# baskettarget.net
KiCad netlist of a schematic drawn in EAGLE
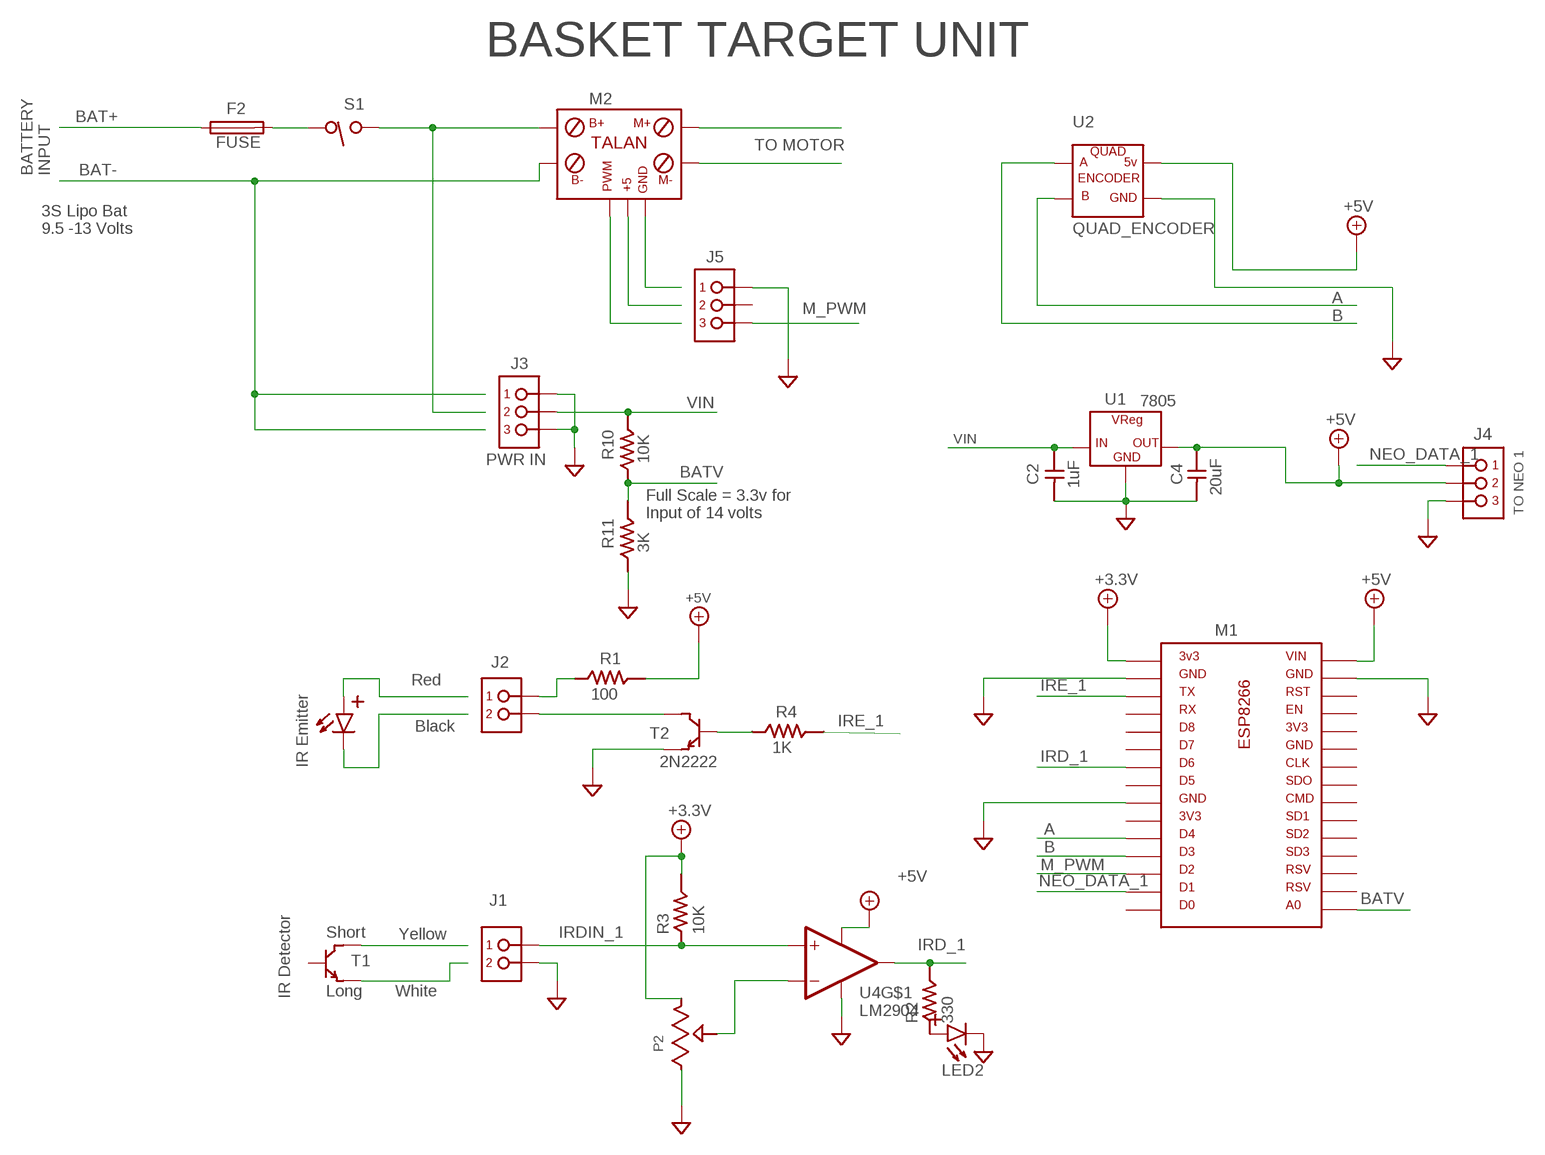
[diagram p0: schematic, sheet 1]

(export (version "E")
  (design (tool "Eeschema 10.0.6"))
  (components
    (comp (ref "C2")
      (value "1uF")
      (footprint "eagle-import:CAP200")
      (libsource (lib "eagle-import") (part "CAP200"))
    )
    (comp (ref "C4")
      (value "20uF")
      (footprint "eagle-import:CAP200")
      (libsource (lib "eagle-import") (part "CAP200"))
    )
    (comp (ref "F2")
      (value "FUSE")
      (footprint "eagle-import:FUSE_HOLDER_WICKMANN-19596")
      (libsource (lib "eagle-import") (part "FUSE19596"))
    )
    (comp (ref "J1")
      (value "PINHDR_1X2-JST")
      (footprint "eagle-import:JST-XH_098_VERT_1X2")
      (libsource (lib "eagle-import") (part "PINHDR_1X2-JST"))
    )
    (comp (ref "J2")
      (value "PINHDR_1X2-JST")
      (footprint "eagle-import:JST-XH_098_VERT_1X2")
      (libsource (lib "eagle-import") (part "PINHDR_1X2-JST"))
    )
    (comp (ref "J3")
      (value "PINHDR_1X3XH-JST")
      (footprint "eagle-import:JST-XH_098_VERT_1X3")
      (libsource (lib "eagle-import") (part "PINHDR_1X3-JSTXH"))
    )
    (comp (ref "J4")
      (value "PINHDR_1X3XH-JST")
      (footprint "eagle-import:JST-XH_098_VERT_1X3")
      (libsource (lib "eagle-import") (part "PINHDR_1X3-JSTXH"))
    )
    (comp (ref "J5")
      (value "PINHDR_1X3XH-JST")
      (footprint "eagle-import:JST-XH_098_VERT_1X3")
      (libsource (lib "eagle-import") (part "PINHDR_1X3-JSTXH"))
    )
    (comp (ref "LED1")
      (value "LEDTH-DIP-100")
      (footprint "eagle-import:LED-TH100")
      (libsource (lib "eagle-import") (part "LEDTH-DIP-100"))
    )
    (comp (ref "LED2")
      (value "LEDTH-DIP-100")
      (footprint "eagle-import:LED-TH100")
      (libsource (lib "eagle-import") (part "LEDTH-DIP-100"))
    )
    (comp (ref "M1")
      (value "ESP8266_MODULE")
      (footprint "eagle-import:ESP8266_MODULE")
      (libsource (lib "eagle-import") (part "ESP8266_MODULE"))
    )
    (comp (ref "M2")
      (value "TALAN")
      (footprint "eagle-import:TALAN_PWM")
      (libsource (lib "eagle-import") (part "TALAN"))
    )
    (comp (ref "P2")
      (value "TRIMPOT-SIP")
      (footprint "eagle-import:TRIMPOT_SIP_100")
      (libsource (lib "eagle-import") (part "TRIMPOT-SIP"))
    )
    (comp (ref "R1")
      (value "100")
      (footprint "eagle-import:R300")
      (libsource (lib "eagle-import") (part "RTHOLE300"))
    )
    (comp (ref "R2")
      (value "330")
      (footprint "eagle-import:R300")
      (libsource (lib "eagle-import") (part "RTHOLE300"))
    )
    (comp (ref "R3")
      (value "10K")
      (footprint "eagle-import:R300")
      (libsource (lib "eagle-import") (part "RTHOLE300"))
    )
    (comp (ref "R4")
      (value "1K")
      (footprint "eagle-import:R300")
      (libsource (lib "eagle-import") (part "RTHOLE300"))
    )
    (comp (ref "R10")
      (value "10K")
      (footprint "eagle-import:R300")
      (libsource (lib "eagle-import") (part "RTHOLE300"))
    )
    (comp (ref "R11")
      (value "3K")
      (footprint "eagle-import:R300")
      (libsource (lib "eagle-import") (part "RTHOLE300"))
    )
    (comp (ref "S1")
      (value "TOGGLE_SWITCH_SPST")
      (footprint "eagle-import:SPST_TOGGLE")
      (libsource (lib "eagle-import") (part "TOGGLE_SWITCH_SPST"))
    )
    (comp (ref "T1")
      (value "T_NPN")
      (footprint "eagle-import:TO-92")
      (libsource (lib "eagle-import") (part "T_NPN"))
    )
    (comp (ref "T2")
      (value "2N2222")
      (footprint "eagle-import:TO-92")
      (libsource (lib "eagle-import") (part "T_NPN"))
    )
    (comp (ref "U1")
      (value "7805")
      (footprint "eagle-import:PINHDR_TH_100_1X3")
      (libsource (lib "eagle-import") (part "VREG-3-DIP"))
    )
    (comp (ref "U2")
      (value "QUAD_ENCODER")
      (footprint "eagle-import:QUAD_ENCODER")
      (libsource (lib "eagle-import") (part "QUAD_ENCODER"))
    )
    (comp (ref "U4")
      (value "LM2904")
      (footprint "eagle-import:DIP8")
      (libsource (lib "eagle-import") (part "LM2904"))
    )
  )
  (nets
    (net (code "1") (name "+3.3V") (class "Default")
      (node (ref "M1") (pin "P$1") (pinfunction "P$1_P$1") (pintype "passive"))
      (node (ref "P2") (pin "P$3") (pinfunction "P$3_P$3") (pintype "passive"))
      (node (ref "R3") (pin "P$2") (pinfunction "2_P$2") (pintype "passive"))
    )
    (net (code "2") (name "+5V") (class "Default")
      (node (ref "C4") (pin "2") (pinfunction "2_2") (pintype "passive"))
      (node (ref "J4") (pin "2") (pinfunction "2_2") (pintype "passive"))
      (node (ref "M1") (pin "P$30") (pinfunction "P$30_P$30") (pintype "passive"))
      (node (ref "R1") (pin "P$2") (pinfunction "2_P$2") (pintype "passive"))
      (node (ref "U1") (pin "3") (pinfunction "OUT_3") (pintype "passive"))
      (node (ref "U2") (pin "5V") (pinfunction "5V_5V") (pintype "passive"))
      (node (ref "U4") (pin "P$8") (pinfunction "P+_P$8") (pintype "passive"))
    )
    (net (code "3") (name "/A") (class "Default")
      (node (ref "M1") (pin "P$11") (pinfunction "P$11_P$11") (pintype "passive"))
      (node (ref "U2") (pin "B") (pinfunction "B_B") (pintype "passive"))
    )
    (net (code "4") (name "/B") (class "Default")
      (node (ref "M1") (pin "P$12") (pinfunction "P$12_P$12") (pintype "passive"))
      (node (ref "U2") (pin "A") (pinfunction "A_A") (pintype "passive"))
    )
    (net (code "5") (name "/BAT+") (class "Default")
      (node (ref "F2") (pin "A") (pinfunction "1_A") (pintype "passive"))
    )
    (net (code "6") (name "/BAT-") (class "Default")
      (node (ref "M2") (pin "B-") (pinfunction "B-_B-") (pintype "passive"))
    )
    (net (code "7") (name "/BATV") (class "Default")
      (node (ref "M1") (pin "P$16") (pinfunction "P$16_P$16") (pintype "passive"))
      (node (ref "R10") (pin "P$1") (pinfunction "1_P$1") (pintype "passive"))
      (node (ref "R11") (pin "P$2") (pinfunction "2_P$2") (pintype "passive"))
    )
    (net (code "8") (name "/IRDIN_1") (class "Default")
      (node (ref "J1") (pin "1") (pinfunction "1_1") (pintype "passive"))
      (node (ref "R3") (pin "P$1") (pinfunction "1_P$1") (pintype "passive"))
      (node (ref "U4") (pin "P$3") (pinfunction "+IN_P$3") (pintype "input"))
    )
    (net (code "9") (name "/IRD_1") (class "Default")
      (node (ref "M1") (pin "P$7") (pinfunction "P$7_P$7") (pintype "passive"))
      (node (ref "R2") (pin "P$2") (pinfunction "2_P$2") (pintype "passive"))
      (node (ref "U4") (pin "P$1") (pinfunction "OUT_P$1") (pintype "output"))
    )
    (net (code "10") (name "/IRE_1") (class "Default")
      (node (ref "M1") (pin "P$3") (pinfunction "P$3_P$3") (pintype "passive"))
      (node (ref "R4") (pin "P$2") (pinfunction "2_P$2") (pintype "passive"))
    )
    (net (code "11") (name "/M_PWM") (class "Default")
      (node (ref "J5") (pin "1") (pinfunction "3_1") (pintype "passive"))
      (node (ref "M1") (pin "P$13") (pinfunction "P$13_P$13") (pintype "passive"))
    )
    (net (code "12") (name "/NEO_DATA_1") (class "Default")
      (node (ref "J4") (pin "3") (pinfunction "1_3") (pintype "passive"))
      (node (ref "M1") (pin "P$14") (pinfunction "P$14_P$14") (pintype "passive"))
    )
    (net (code "13") (name "/VIN") (class "Default")
      (node (ref "C2") (pin "2") (pinfunction "2_2") (pintype "passive"))
      (node (ref "J3") (pin "2") (pinfunction "2_2") (pintype "passive"))
      (node (ref "R10") (pin "P$2") (pinfunction "2_P$2") (pintype "passive"))
      (node (ref "U1") (pin "1") (pinfunction "IN_1") (pintype "passive"))
    )
    (net (code "14") (name "GND") (class "Default")
      (node (ref "C2") (pin "1") (pinfunction "1_1") (pintype "passive"))
      (node (ref "C4") (pin "1") (pinfunction "1_1") (pintype "passive"))
      (node (ref "J1") (pin "2") (pinfunction "2_2") (pintype "passive"))
      (node (ref "J3") (pin "1") (pinfunction "3_1") (pintype "passive"))
      (node (ref "J3") (pin "3") (pinfunction "1_3") (pintype "passive"))
      (node (ref "J4") (pin "1") (pinfunction "3_1") (pintype "passive"))
      (node (ref "J5") (pin "3") (pinfunction "1_3") (pintype "passive"))
      (node (ref "LED2") (pin "P$2") (pinfunction "CATHODE_P$2") (pintype "passive"))
      (node (ref "M1") (pin "P$2") (pinfunction "P$2_P$2") (pintype "passive"))
      (node (ref "M1") (pin "P$29") (pinfunction "P$29_P$29") (pintype "passive"))
      (node (ref "M1") (pin "P$9") (pinfunction "P$9_P$9") (pintype "passive"))
      (node (ref "P2") (pin "P$1") (pinfunction "P$1_P$1") (pintype "passive"))
      (node (ref "R11") (pin "P$1") (pinfunction "1_P$1") (pintype "passive"))
      (node (ref "T2") (pin "P$3") (pinfunction "EMITTER_P$3") (pintype "passive"))
      (node (ref "U1") (pin "2") (pinfunction "GND_2") (pintype "passive"))
      (node (ref "U2") (pin "GND") (pinfunction "GND_GND") (pintype "passive"))
      (node (ref "U4") (pin "P$4") (pinfunction "P-_P$4") (pintype "passive"))
    )
    (net (code "15") (name "Net-(F2-2)") (class "Default")
      (node (ref "F2") (pin "B") (pinfunction "2_B") (pintype "passive"))
      (node (ref "S1") (pin "P$1") (pinfunction "P$1_P$1") (pintype "passive"))
    )
    (net (code "16") (name "Net-(LED2-ANODE)") (class "Default")
      (node (ref "LED2") (pin "P$1") (pinfunction "ANODE_P$1") (pintype "passive"))
      (node (ref "R2") (pin "P$1") (pinfunction "1_P$1") (pintype "passive"))
    )
    (net (code "17") (name "Net-(M2-PadB+)") (class "Default")
      (node (ref "M2") (pin "B+") (pinfunction "B+_B+") (pintype "passive"))
      (node (ref "S1") (pin "P$3") (pinfunction "P$3_P$3") (pintype "passive"))
    )
    (net (code "18") (name "Net-(R1-1)") (class "Default")
      (node (ref "J2") (pin "1") (pinfunction "1_1") (pintype "passive"))
      (node (ref "R1") (pin "P$1") (pinfunction "1_P$1") (pintype "passive"))
    )
    (net (code "19") (name "Net-(R4-1)") (class "Default")
      (node (ref "R4") (pin "P$1") (pinfunction "1_P$1") (pintype "passive"))
      (node (ref "T2") (pin "P$2") (pinfunction "BASE_P$2") (pintype "passive"))
    )
    (net (code "20") (name "Net-(T2-COLLECTOR)") (class "Default")
      (node (ref "J2") (pin "2") (pinfunction "2_2") (pintype "passive"))
      (node (ref "T2") (pin "P$1") (pinfunction "COLLECTOR_P$1") (pintype "passive"))
    )
    (net (code "21") (name "Net-(U4A--IN)") (class "Default")
      (node (ref "P2") (pin "P$2") (pinfunction "P$2_P$2") (pintype "passive"))
      (node (ref "U4") (pin "P$2") (pinfunction "-IN_P$2") (pintype "input"))
    )
    (net (code "22") (name "unconnected-(J5-Pad2)") (class "Default")
      (node (ref "J5") (pin "2") (pinfunction "2_2") (pintype "passive"))
    )
    (net (code "23") (name "unconnected-(LED1-ANODE-PadP$1)") (class "Default")
      (node (ref "LED1") (pin "P$1") (pinfunction "ANODE_P$1") (pintype "passive"))
    )
    (net (code "24") (name "unconnected-(LED1-CATHODE-PadP$2)") (class "Default")
      (node (ref "LED1") (pin "P$2") (pinfunction "CATHODE_P$2") (pintype "passive"))
    )
    (net (code "25") (name "unconnected-(M1-PadP$4)") (class "Default")
      (node (ref "M1") (pin "P$4") (pinfunction "P$4_P$4") (pintype "passive"))
    )
    (net (code "26") (name "unconnected-(M1-PadP$5)") (class "Default")
      (node (ref "M1") (pin "P$5") (pinfunction "P$5_P$5") (pintype "passive"))
    )
    (net (code "27") (name "unconnected-(M1-PadP$6)") (class "Default")
      (node (ref "M1") (pin "P$6") (pinfunction "P$6_P$6") (pintype "passive"))
    )
    (net (code "28") (name "unconnected-(M1-PadP$8)") (class "Default")
      (node (ref "M1") (pin "P$8") (pinfunction "P$8_P$8") (pintype "passive"))
    )
    (net (code "29") (name "unconnected-(M1-PadP$10)") (class "Default")
      (node (ref "M1") (pin "P$10") (pinfunction "P$10_P$10") (pintype "passive"))
    )
    (net (code "30") (name "unconnected-(M1-PadP$15)") (class "Default")
      (node (ref "M1") (pin "P$15") (pinfunction "P$15_P$15") (pintype "passive"))
    )
    (net (code "31") (name "unconnected-(M1-PadP$17)") (class "Default")
      (node (ref "M1") (pin "P$17") (pinfunction "P$17_P$17") (pintype "passive"))
    )
    (net (code "32") (name "unconnected-(M1-PadP$18)") (class "Default")
      (node (ref "M1") (pin "P$18") (pinfunction "P$18_P$18") (pintype "passive"))
    )
    (net (code "33") (name "unconnected-(M1-PadP$19)") (class "Default")
      (node (ref "M1") (pin "P$19") (pinfunction "P$19_P$19") (pintype "passive"))
    )
    (net (code "34") (name "unconnected-(M1-PadP$20)") (class "Default")
      (node (ref "M1") (pin "P$20") (pinfunction "P$20_P$20") (pintype "passive"))
    )
    (net (code "35") (name "unconnected-(M1-PadP$21)") (class "Default")
      (node (ref "M1") (pin "P$21") (pinfunction "P$21_P$21") (pintype "passive"))
    )
    (net (code "36") (name "unconnected-(M1-PadP$22)") (class "Default")
      (node (ref "M1") (pin "P$22") (pinfunction "P$22_P$22") (pintype "passive"))
    )
    (net (code "37") (name "unconnected-(M1-PadP$23)") (class "Default")
      (node (ref "M1") (pin "P$23") (pinfunction "P$23_P$23") (pintype "passive"))
    )
    (net (code "38") (name "unconnected-(M1-PadP$24)") (class "Default")
      (node (ref "M1") (pin "P$24") (pinfunction "P$24_P$24") (pintype "passive"))
    )
    (net (code "39") (name "unconnected-(M1-PadP$25)") (class "Default")
      (node (ref "M1") (pin "P$25") (pinfunction "P$25_P$25") (pintype "passive"))
    )
    (net (code "40") (name "unconnected-(M1-PadP$26)") (class "Default")
      (node (ref "M1") (pin "P$26") (pinfunction "P$26_P$26") (pintype "passive"))
    )
    (net (code "41") (name "unconnected-(M1-PadP$27)") (class "Default")
      (node (ref "M1") (pin "P$27") (pinfunction "P$27_P$27") (pintype "passive"))
    )
    (net (code "42") (name "unconnected-(M1-PadP$28)") (class "Default")
      (node (ref "M1") (pin "P$28") (pinfunction "P$28_P$28") (pintype "passive"))
    )
    (net (code "43") (name "unconnected-(M2-Pad5V)") (class "Default")
      (node (ref "M2") (pin "5V") (pinfunction "5V_5V") (pintype "passive"))
    )
    (net (code "44") (name "unconnected-(M2-PadGND)") (class "Default")
      (node (ref "M2") (pin "GND") (pinfunction "GND_GND") (pintype "passive"))
    )
    (net (code "45") (name "unconnected-(M2-PadM+)") (class "Default")
      (node (ref "M2") (pin "M+") (pinfunction "M+_M+") (pintype "passive"))
    )
    (net (code "46") (name "unconnected-(M2-PadM-)") (class "Default")
      (node (ref "M2") (pin "M-") (pinfunction "M-_M-") (pintype "passive"))
    )
    (net (code "47") (name "unconnected-(M2-PadPWM)") (class "Default")
      (node (ref "M2") (pin "PWM") (pinfunction "PWM_PWM") (pintype "passive"))
    )
    (net (code "48") (name "unconnected-(S1-PadP$2)") (class "Default")
      (node (ref "S1") (pin "P$2") (pinfunction "P$2_P$2") (pintype "passive"))
    )
    (net (code "49") (name "unconnected-(T1-BASE-PadP$2)") (class "Default")
      (node (ref "T1") (pin "P$2") (pinfunction "BASE_P$2") (pintype "passive"))
    )
    (net (code "50") (name "unconnected-(T1-COLLECTOR-PadP$1)") (class "Default")
      (node (ref "T1") (pin "P$1") (pinfunction "COLLECTOR_P$1") (pintype "passive"))
    )
    (net (code "51") (name "unconnected-(T1-EMITTER-PadP$3)") (class "Default")
      (node (ref "T1") (pin "P$3") (pinfunction "EMITTER_P$3") (pintype "passive"))
    )
  )
)
